# test_platform.net
KiCad netlist of a schematic drawn in EAGLE
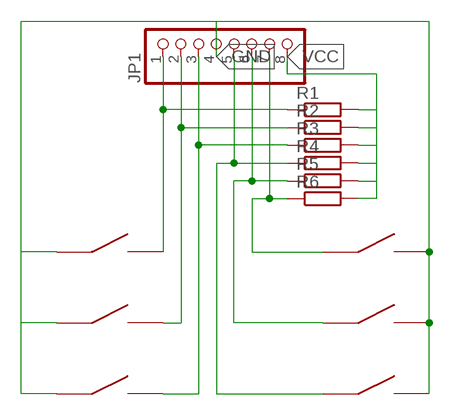
[diagram p0: schematic, sheet 1]

(export (version "E")
  (design (tool "Eeschema 10.0.6"))
  (components
    (comp (ref "JP1")
      (value "PINHD-1X8BIG")
      (footprint "eagle-import:1X08-BIG")
      (libsource (lib "eagle-import") (part "PINHD-1X8BIG"))
    )
    (comp (ref "R1")
      (value "R-EU_M0805")
      (footprint "eagle-import:M0805")
      (libsource (lib "eagle-import") (part "R-EU_M0805"))
    )
    (comp (ref "R2")
      (value "R-EU_M0805")
      (footprint "eagle-import:M0805")
      (libsource (lib "eagle-import") (part "R-EU_M0805"))
    )
    (comp (ref "R3")
      (value "R-EU_M0805")
      (footprint "eagle-import:M0805")
      (libsource (lib "eagle-import") (part "R-EU_M0805"))
    )
    (comp (ref "R4")
      (value "R-EU_M0805")
      (footprint "eagle-import:M0805")
      (libsource (lib "eagle-import") (part "R-EU_M0805"))
    )
    (comp (ref "R5")
      (value "R-EU_M0805")
      (footprint "eagle-import:M0805")
      (libsource (lib "eagle-import") (part "R-EU_M0805"))
    )
    (comp (ref "R6")
      (value "R-EU_M0805")
      (footprint "eagle-import:M0805")
      (libsource (lib "eagle-import") (part "R-EU_M0805"))
    )
    (comp (ref "U$1")
      (value "SMT_BUTTON")
      (footprint "eagle-import:SMT-BUTTON")
      (libsource (lib "eagle-import") (part "SMT_BUTTON"))
    )
    (comp (ref "U$2")
      (value "SMT_BUTTON")
      (footprint "eagle-import:SMT-BUTTON")
      (libsource (lib "eagle-import") (part "SMT_BUTTON"))
    )
    (comp (ref "U$3")
      (value "SMT_BUTTON")
      (footprint "eagle-import:SMT-BUTTON")
      (libsource (lib "eagle-import") (part "SMT_BUTTON"))
    )
    (comp (ref "U$4")
      (value "SMT_BUTTON")
      (footprint "eagle-import:SMT-BUTTON")
      (libsource (lib "eagle-import") (part "SMT_BUTTON"))
    )
    (comp (ref "U$5")
      (value "SMT_BUTTON")
      (footprint "eagle-import:SMT-BUTTON")
      (libsource (lib "eagle-import") (part "SMT_BUTTON"))
    )
    (comp (ref "U$6")
      (value "SMT_BUTTON")
      (footprint "eagle-import:SMT-BUTTON")
      (libsource (lib "eagle-import") (part "SMT_BUTTON"))
    )
  )
  (nets
    (net (code "1") (name "GND") (class "Default")
      (node (ref "JP1") (pin "4") (pinfunction "4_4") (pintype "passive"))
      (node (ref "U$1") (pin "A1") (pinfunction "A_A1") (pintype "bidirectional"))
      (node (ref "U$1") (pin "A2") (pinfunction "A_A2") (pintype "bidirectional"))
      (node (ref "U$2") (pin "A1") (pinfunction "A_A1") (pintype "bidirectional"))
      (node (ref "U$2") (pin "A2") (pinfunction "A_A2") (pintype "bidirectional"))
      (node (ref "U$3") (pin "A1") (pinfunction "A_A1") (pintype "bidirectional"))
      (node (ref "U$3") (pin "A2") (pinfunction "A_A2") (pintype "bidirectional"))
      (node (ref "U$4") (pin "B1") (pinfunction "B_B1") (pintype "bidirectional"))
      (node (ref "U$4") (pin "B2") (pinfunction "B_B2") (pintype "bidirectional"))
      (node (ref "U$5") (pin "B1") (pinfunction "B_B1") (pintype "bidirectional"))
      (node (ref "U$5") (pin "B2") (pinfunction "B_B2") (pintype "bidirectional"))
      (node (ref "U$6") (pin "B1") (pinfunction "B_B1") (pintype "bidirectional"))
      (node (ref "U$6") (pin "B2") (pinfunction "B_B2") (pintype "bidirectional"))
    )
    (net (code "2") (name "Net-(JP1-Pad1)") (class "Default")
      (node (ref "JP1") (pin "1") (pinfunction "1_1") (pintype "passive"))
      (node (ref "R1") (pin "1") (pinfunction "1_1") (pintype "passive"))
      (node (ref "U$1") (pin "B1") (pinfunction "B_B1") (pintype "bidirectional"))
      (node (ref "U$1") (pin "B2") (pinfunction "B_B2") (pintype "bidirectional"))
    )
    (net (code "3") (name "Net-(JP1-Pad2)") (class "Default")
      (node (ref "JP1") (pin "2") (pinfunction "2_2") (pintype "passive"))
      (node (ref "R2") (pin "1") (pinfunction "1_1") (pintype "passive"))
      (node (ref "U$2") (pin "B1") (pinfunction "B_B1") (pintype "bidirectional"))
      (node (ref "U$2") (pin "B2") (pinfunction "B_B2") (pintype "bidirectional"))
    )
    (net (code "4") (name "Net-(JP1-Pad3)") (class "Default")
      (node (ref "JP1") (pin "3") (pinfunction "3_3") (pintype "passive"))
      (node (ref "R3") (pin "1") (pinfunction "1_1") (pintype "passive"))
      (node (ref "U$3") (pin "B1") (pinfunction "B_B1") (pintype "bidirectional"))
      (node (ref "U$3") (pin "B2") (pinfunction "B_B2") (pintype "bidirectional"))
    )
    (net (code "5") (name "Net-(JP1-Pad5)") (class "Default")
      (node (ref "JP1") (pin "5") (pinfunction "5_5") (pintype "passive"))
      (node (ref "R4") (pin "1") (pinfunction "1_1") (pintype "passive"))
      (node (ref "U$4") (pin "A1") (pinfunction "A_A1") (pintype "bidirectional"))
      (node (ref "U$4") (pin "A2") (pinfunction "A_A2") (pintype "bidirectional"))
    )
    (net (code "6") (name "Net-(JP1-Pad6)") (class "Default")
      (node (ref "JP1") (pin "6") (pinfunction "6_6") (pintype "passive"))
      (node (ref "R5") (pin "1") (pinfunction "1_1") (pintype "passive"))
      (node (ref "U$5") (pin "A1") (pinfunction "A_A1") (pintype "bidirectional"))
      (node (ref "U$5") (pin "A2") (pinfunction "A_A2") (pintype "bidirectional"))
    )
    (net (code "7") (name "Net-(JP1-Pad7)") (class "Default")
      (node (ref "JP1") (pin "7") (pinfunction "7_7") (pintype "passive"))
      (node (ref "R6") (pin "1") (pinfunction "1_1") (pintype "passive"))
      (node (ref "U$6") (pin "A1") (pinfunction "A_A1") (pintype "bidirectional"))
      (node (ref "U$6") (pin "A2") (pinfunction "A_A2") (pintype "bidirectional"))
    )
    (net (code "8") (name "VCC") (class "Default")
      (node (ref "JP1") (pin "8") (pinfunction "8_8") (pintype "passive"))
      (node (ref "R1") (pin "2") (pinfunction "2_2") (pintype "passive"))
      (node (ref "R2") (pin "2") (pinfunction "2_2") (pintype "passive"))
      (node (ref "R3") (pin "2") (pinfunction "2_2") (pintype "passive"))
      (node (ref "R4") (pin "2") (pinfunction "2_2") (pintype "passive"))
      (node (ref "R5") (pin "2") (pinfunction "2_2") (pintype "passive"))
      (node (ref "R6") (pin "2") (pinfunction "2_2") (pintype "passive"))
    )
  )
)
